# AOut_Isolator.net
KiCad netlist of a schematic drawn in Altium Designer
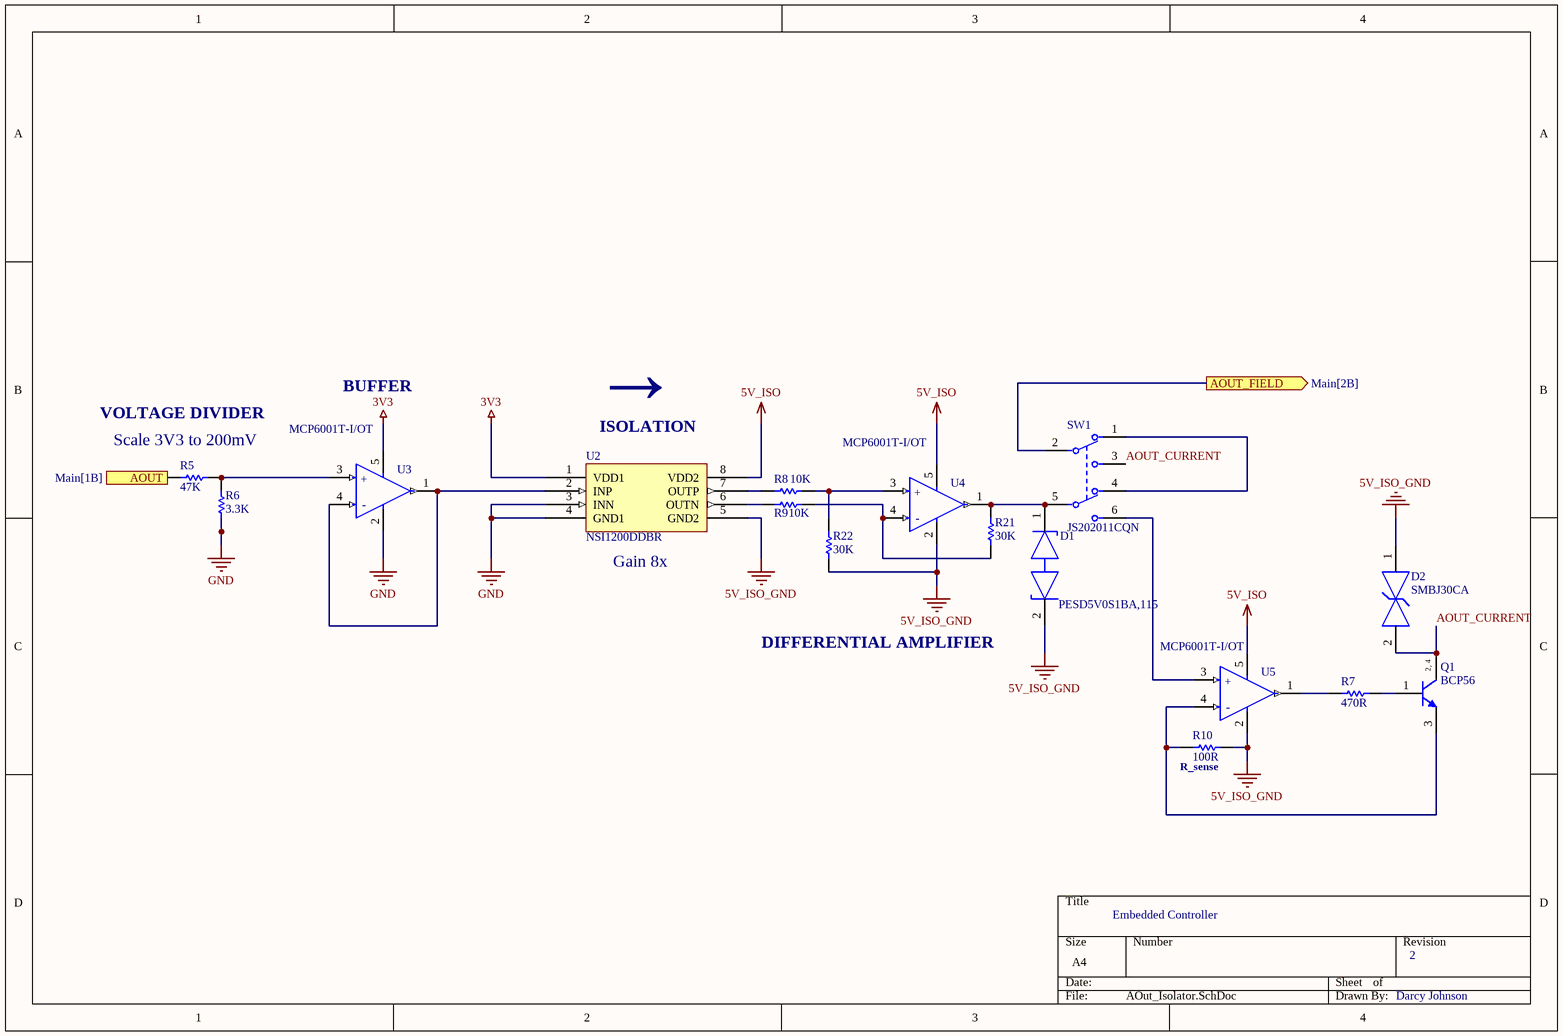
[diagram p0: AOut_Isolator.SchDoc]

(export (version "E")
  (design (tool "Eeschema 10.0.6"))
  (components
    (comp (ref "D1")
      (value "PESD5V0S1BA,115")
      (footprint "FP-SOD323-CA-MFG")
      (description "TVS DIODE 5V 14V SOD323")
      (libsource (lib "Altium Content Vault") (part "f6dbb2535d6b2d347ec798cb4d032a4"))
    )
    (comp (ref "D2")
      (value "SMBJ30CA")
      (footprint "FP-SMBJ30CAHE3-52-MFG")
      (description "TVS DIODE 30V 48.4V DO214AA")
      (fields
        (field (name "OCTOPART") "https://octopart.com/smbj30cahe3%2F52-vishay-43725255")
        (field (name "MANUFACTURER") "Vishay Semiconductor Diodes Division")
      )
      (libsource (lib "Altium Content Vault") (part "876f4347bf90aa6f500f43e3cd03972"))
    )
    (comp (ref "Q1")
      (value "BCP56")
      (footprint "ONSC-SOT-223-4-318E-04_V")
      (description "NPN Silicon Epitaxial Transistor, 4-Pin SOT-223, Pb-Free, Tape and Reel")
      (fields (field (name "PARTNUMBER") "SBCP56T1G") (field (name "MANUFACTURER") "On Semiconductor"))
      (libsource (lib "Altium Content Vault") (part "ONSC-NPN-B1C2E3C4-4"))
    )
    (comp (ref "R5")
      (value "47K")
      (footprint "RESC1608X55X30NL15T15")
      (description "Chip Resistor, 47 KOhm, +/- 1%, 0.1 W, -55 to 155 degC, 0603 (1608 Metric), RoHS, Tape and Reel")
      (libsource (lib "Altium Content Vault") (part "RES-2"))
    )
    (comp (ref "R6")
      (value "3.3K")
      (footprint "RESC1609X55X30ML15T15")
      (description "Chip Resistors, 3.3 KOhm, +/- 1%, 0.1 W, 0603 (1608 Metric), -55 to 155 degC, RoHS, Tape and Reel")
      (fields (field (name "MANUFACTURER") "Panasonic") (field (name "TOLERANCE") "1%"))
      (libsource (lib "Altium Content Vault") (part "RES-2"))
    )
    (comp (ref "R7")
      (value "470R")
      (footprint "RESC1608X55X30NL15T15")
      (fields (field (name "TOLERANCE") "5%"))
      (libsource (lib "Altium Content Vault") (part "RES-2"))
    )
    (comp (ref "R8")
      (value "10K")
      (footprint "RESC1609X55X30LL15T15")
      (description "Chip Resistor, 10 KOhm, +/- 1%, 0.1 W, -55 to 155 degC, 0603 (1608 Metric), RoHS, Tape and Reel")
      (fields (field (name "TOLERANCE") "1%") (field (name "MANUFACTURER") "Panasonic"))
      (libsource (lib "Altium Content Vault") (part "RES-2"))
    )
    (comp (ref "R9")
      (value "10K")
      (footprint "RESC1609X55X30LL15T15")
      (description "Chip Resistor, 10 KOhm, +/- 1%, 0.1 W, -55 to 155 degC, 0603 (1608 Metric), RoHS, Tape and Reel")
      (fields (field (name "TOLERANCE") "1%") (field (name "MANUFACTURER") "Panasonic"))
      (libsource (lib "Altium Content Vault") (part "RES-2"))
    )
    (comp (ref "R10")
      (value "100R")
      (footprint "RESC3216X70X50NL05T20")
      (fields (field (name "PART NUMBER") "ERJ-8GEYJ241V") (field (name "MANUFACTURER") "Panasonic"))
      (libsource (lib "Altium Content Vault") (part "RES"))
    )
    (comp (ref "R21")
      (value "30K")
      (footprint "RESC1608X55X30LL15T15")
      (fields (field (name "PART NUMBER") "ERJ-3GEYJ303V") (field (name "MANUFACTURER") "Panasonic"))
      (libsource (lib "Altium Content Vault") (part "RES"))
    )
    (comp (ref "R22")
      (value "30K")
      (footprint "RESC1608X55X30LL15T15")
      (fields (field (name "PART NUMBER") "ERJ-3GEYJ303V") (field (name "MANUFACTURER") "Panasonic"))
      (libsource (lib "Altium Content Vault") (part "RES"))
    )
    (comp (ref "SW1")
      (value "JS202011CQN")
      (footprint "FP-JS202011CQN-MFG - duplicate")
      (description "SWITCH SLIDE DPDT 300MA 6V")
      (libsource (lib "JS202011CQN ") (part "CMP-10038-000022-1_1"))
    )
    (comp (ref "U2")
      (value "NSI1200DDBR")
      (footprint "NSI1200DDBR")
      (description "High Reliability Reinforced Isolated Amplifier")
      (fields (field (name "MANUFACTURER") "Novosense"))
      (libsource (lib "nsi1200") (part "NSI1200DDBR"))
    )
    (comp (ref "U3")
      (value "MCP6001T-I/OT")
      (footprint "FP-C04-091-OT-IPC_A")
      (description "IC OPAMP GP 1 CIRCUIT SOT23-5")
      (fields (field (name "VOLTAGE") "6V"))
      (libsource (lib "Altium Content Vault") (part "c8a8c153b9e84e05c1733c8ea85bdd9"))
    )
    (comp (ref "U4")
      (value "MCP6001T-I/OT")
      (footprint "FP-C04-091-OT-IPC_A")
      (description "IC OPAMP GP 1 CIRCUIT SOT23-5")
      (fields (field (name "VOLTAGE") "6V"))
      (libsource (lib "Altium Content Vault") (part "c8a8c153b9e84e05c1733c8ea85bdd9"))
    )
    (comp (ref "U5")
      (value "MCP6001T-I/OT")
      (footprint "FP-C04-091-OT-IPC_A")
      (description "IC OPAMP GP 1 CIRCUIT SOT23-5")
      (fields (field (name "VOLTAGE") "6V"))
      (libsource (lib "Altium Content Vault") (part "c8a8c153b9e84e05c1733c8ea85bdd9"))
    )
  )
  (nets
    (net (code "1") (name "/AOUT") (class "Default")
      (node (ref "R5") (pin "1") (pinfunction "1_1") (pintype "passive"))
    )
    (net (code "2") (name "/AOUT_CURRENT") (class "Default")
      (node (ref "D2") (pin "2") (pinfunction "2_2") (pintype "passive"))
      (node (ref "Q1") (pin "2") (pinfunction "C_2") (pintype "passive"))
      (node (ref "Q1") (pin "4") (pinfunction "C_4") (pintype "passive"))
      (node (ref "SW1") (pin "3") (pinfunction "3_3") (pintype "passive"))
    )
    (net (code "3") (name "/AOUT_FIELD") (class "Default")
      (node (ref "SW1") (pin "2") (pinfunction "2_2") (pintype "passive"))
    )
    (net (code "4") (name "3V3") (class "Default")
      (node (ref "U2") (pin "1") (pinfunction "VDD1_1") (pintype "power_in"))
      (node (ref "U3") (pin "5") (pinfunction "VDD_5") (pintype "power_in"))
    )
    (net (code "5") (name "5V_ISO") (class "Default")
      (node (ref "U2") (pin "8") (pinfunction "VDD2_8") (pintype "power_in"))
      (node (ref "U4") (pin "5") (pinfunction "VDD_5") (pintype "power_in"))
      (node (ref "U5") (pin "5") (pinfunction "VDD_5") (pintype "power_in"))
    )
    (net (code "6") (name "5V_ISO_GND") (class "Default")
      (node (ref "D1") (pin "2") (pinfunction "K2_2") (pintype "passive"))
      (node (ref "D2") (pin "1") (pinfunction "1_1") (pintype "passive"))
      (node (ref "R10") (pin "1") (pinfunction "1_1") (pintype "passive"))
      (node (ref "R22") (pin "2") (pinfunction "2_2") (pintype "passive"))
      (node (ref "U2") (pin "5") (pinfunction "GND2_5") (pintype "power_in"))
      (node (ref "U4") (pin "2") (pinfunction "VSS_2") (pintype "power_in"))
      (node (ref "U5") (pin "2") (pinfunction "VSS_2") (pintype "power_in"))
    )
    (net (code "7") (name "GND") (class "Default")
      (node (ref "R6") (pin "2") (pinfunction "2_2") (pintype "passive"))
      (node (ref "U2") (pin "3") (pinfunction "INN_3") (pintype "input"))
      (node (ref "U2") (pin "4") (pinfunction "GND1_4") (pintype "power_in"))
      (node (ref "U3") (pin "2") (pinfunction "VSS_2") (pintype "power_in"))
    )
    (net (code "8") (name "Net-(D1-K1)") (class "Default")
      (node (ref "D1") (pin "1") (pinfunction "K1_1") (pintype "passive"))
      (node (ref "R21") (pin "1") (pinfunction "1_1") (pintype "passive"))
      (node (ref "SW1") (pin "5") (pinfunction "5_5") (pintype "passive"))
      (node (ref "U4") (pin "1") (pinfunction "VOUT_1") (pintype "output"))
    )
    (net (code "9") (name "Net-(Q1-B)") (class "Default")
      (node (ref "Q1") (pin "1") (pinfunction "B_1") (pintype "passive"))
      (node (ref "R7") (pin "2") (pinfunction "2_2") (pintype "passive"))
    )
    (net (code "10") (name "Net-(Q1-E)") (class "Default")
      (node (ref "Q1") (pin "3") (pinfunction "E_3") (pintype "passive"))
      (node (ref "R10") (pin "2") (pinfunction "2_2") (pintype "passive"))
      (node (ref "U5") (pin "4") (pinfunction "VIN-_4") (pintype "input"))
    )
    (net (code "11") (name "Net-(SW1-Pad1)") (class "Default")
      (node (ref "SW1") (pin "1") (pinfunction "1_1") (pintype "passive"))
      (node (ref "SW1") (pin "4") (pinfunction "4_4") (pintype "passive"))
    )
    (net (code "12") (name "Net-(U2-INP)") (class "Default")
      (node (ref "U2") (pin "2") (pinfunction "INP_2") (pintype "input"))
      (node (ref "U3") (pin "1") (pinfunction "VOUT_1") (pintype "output"))
      (node (ref "U3") (pin "4") (pinfunction "VIN-_4") (pintype "input"))
    )
    (net (code "13") (name "Net-(U2-OUTN)") (class "Default")
      (node (ref "R9") (pin "1") (pinfunction "1_1") (pintype "passive"))
      (node (ref "U2") (pin "6") (pinfunction "OUTN_6") (pintype "output"))
    )
    (net (code "14") (name "Net-(U2-OUTP)") (class "Default")
      (node (ref "R8") (pin "1") (pinfunction "1_1") (pintype "passive"))
      (node (ref "U2") (pin "7") (pinfunction "OUTP_7") (pintype "output"))
    )
    (net (code "15") (name "Net-(U3-VIN+)") (class "Default")
      (node (ref "R5") (pin "2") (pinfunction "2_2") (pintype "passive"))
      (node (ref "R6") (pin "1") (pinfunction "1_1") (pintype "passive"))
      (node (ref "U3") (pin "3") (pinfunction "VIN+_3") (pintype "input"))
    )
    (net (code "16") (name "Net-(U4-VIN+)") (class "Default")
      (node (ref "R22") (pin "1") (pinfunction "1_1") (pintype "passive"))
      (node (ref "R8") (pin "2") (pinfunction "2_2") (pintype "passive"))
      (node (ref "U4") (pin "3") (pinfunction "VIN+_3") (pintype "input"))
    )
    (net (code "17") (name "Net-(U4-VIN-)") (class "Default")
      (node (ref "R21") (pin "2") (pinfunction "2_2") (pintype "passive"))
      (node (ref "R9") (pin "2") (pinfunction "2_2") (pintype "passive"))
      (node (ref "U4") (pin "4") (pinfunction "VIN-_4") (pintype "input"))
    )
    (net (code "18") (name "Net-(U5-VIN+)") (class "Default")
      (node (ref "SW1") (pin "6") (pinfunction "6_6") (pintype "passive"))
      (node (ref "U5") (pin "3") (pinfunction "VIN+_3") (pintype "input"))
    )
    (net (code "19") (name "Net-(U5-VOUT)") (class "Default")
      (node (ref "R7") (pin "1") (pinfunction "1_1") (pintype "passive"))
      (node (ref "U5") (pin "1") (pinfunction "VOUT_1") (pintype "output"))
    )
  )
)
